# pcb-pick-plaz-ring.net
KiCad netlist of a schematic drawn in EAGLE
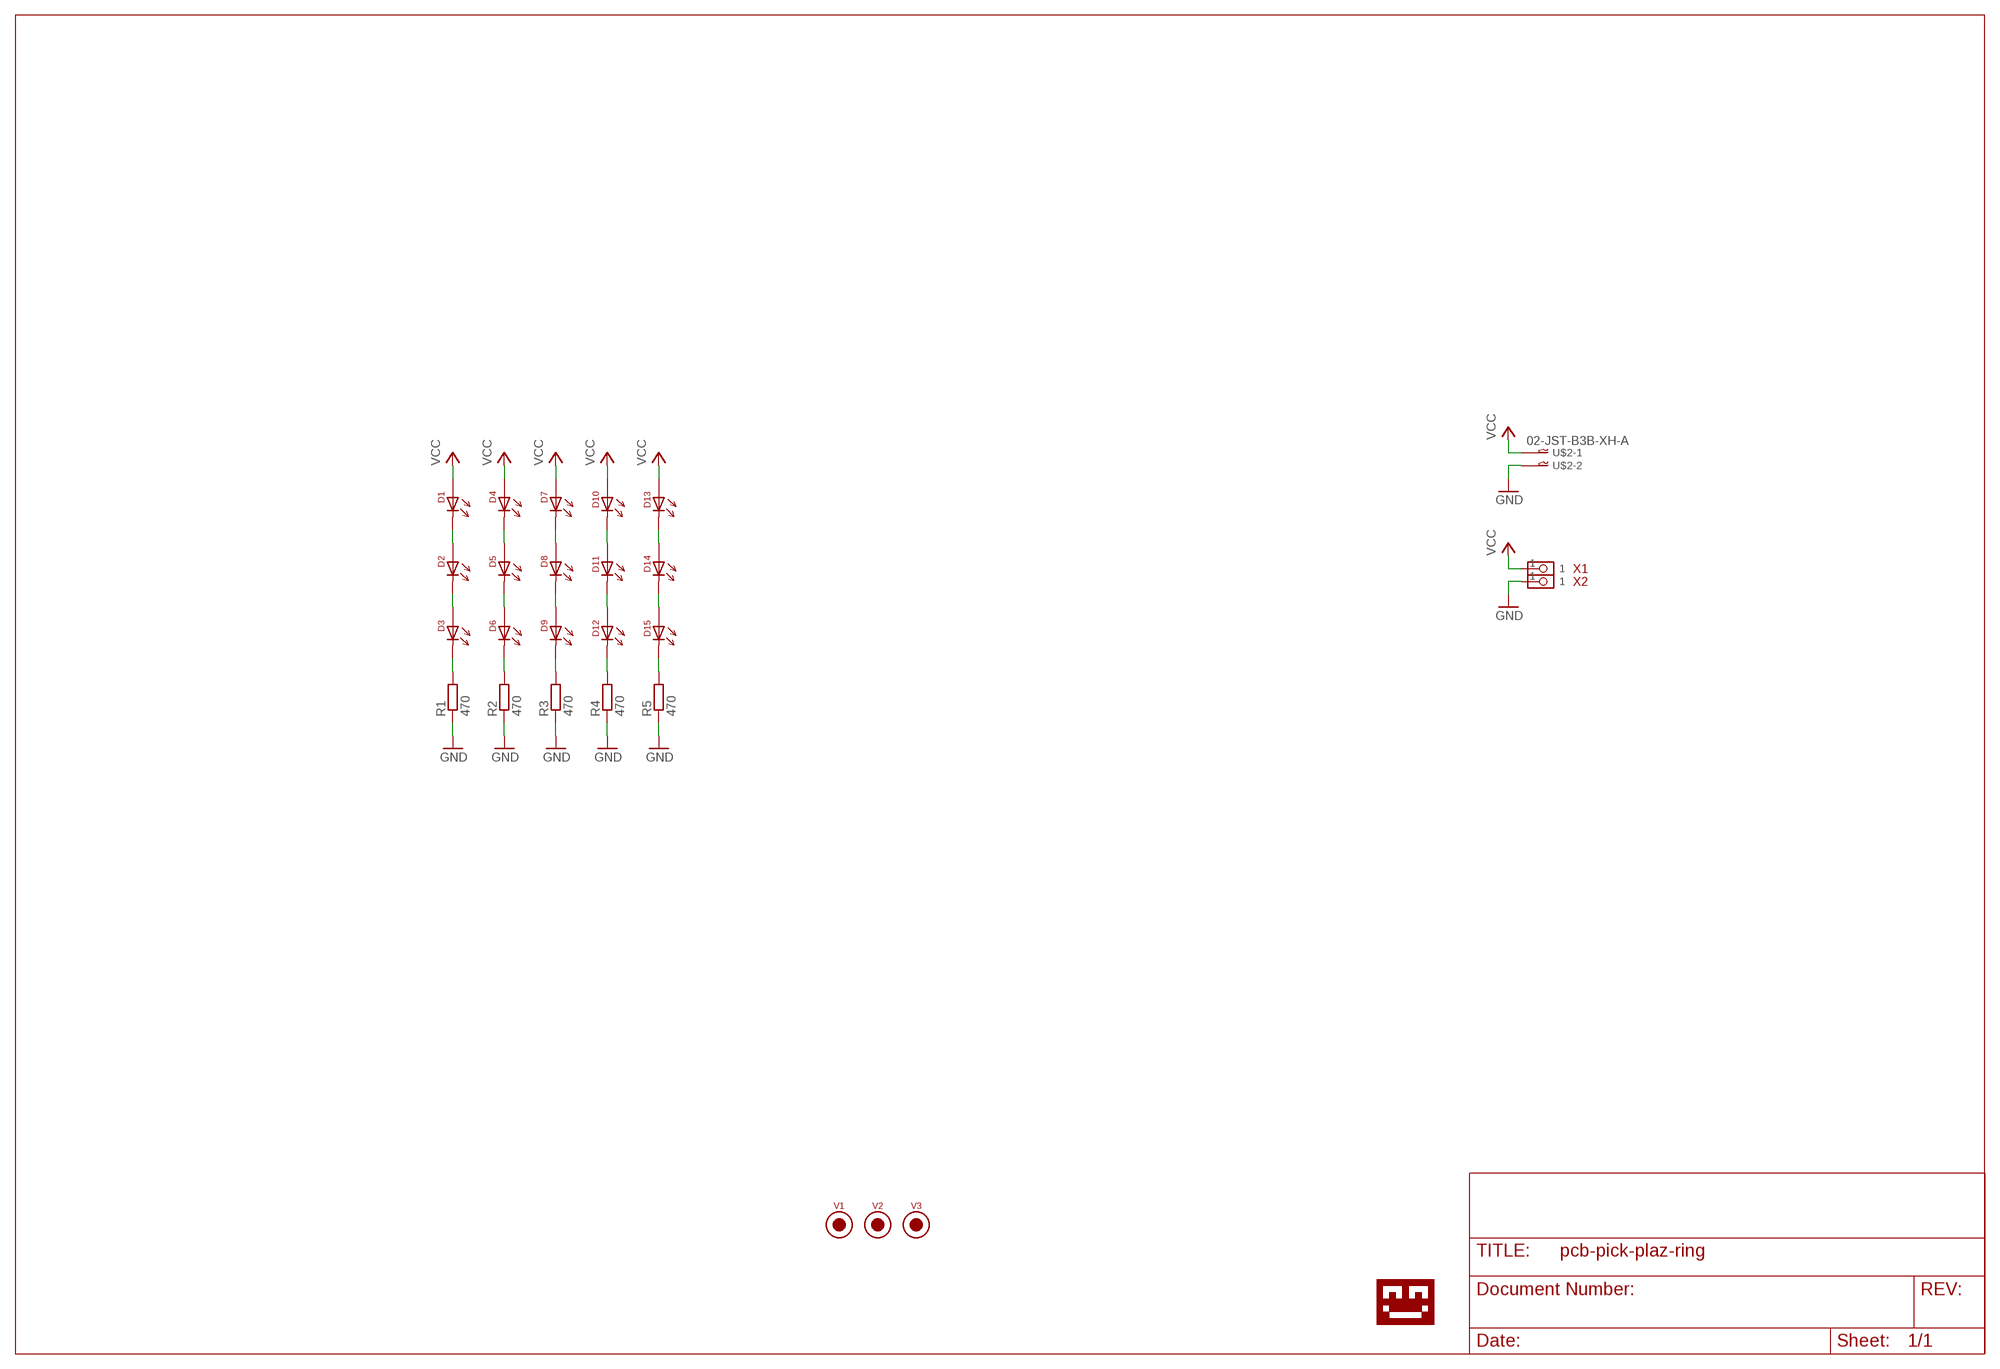
[diagram p0: schematic, sheet 1]

(export (version "E")
  (design (tool "Eeschema 10.0.6"))
  (components
    (comp (ref "D1")
      (value "LED-5730")
      (footprint "eagle-import:5730-LED")
      (libsource (lib "eagle-import") (part "LED-5730"))
    )
    (comp (ref "D2")
      (value "LED-5730")
      (footprint "eagle-import:5730-LED")
      (libsource (lib "eagle-import") (part "LED-5730"))
    )
    (comp (ref "D3")
      (value "LED-5730")
      (footprint "eagle-import:5730-LED")
      (libsource (lib "eagle-import") (part "LED-5730"))
    )
    (comp (ref "D4")
      (value "LED-5730")
      (footprint "eagle-import:5730-LED")
      (libsource (lib "eagle-import") (part "LED-5730"))
    )
    (comp (ref "D5")
      (value "LED-5730")
      (footprint "eagle-import:5730-LED")
      (libsource (lib "eagle-import") (part "LED-5730"))
    )
    (comp (ref "D6")
      (value "LED-5730")
      (footprint "eagle-import:5730-LED")
      (libsource (lib "eagle-import") (part "LED-5730"))
    )
    (comp (ref "D7")
      (value "LED-5730")
      (footprint "eagle-import:5730-LED")
      (libsource (lib "eagle-import") (part "LED-5730"))
    )
    (comp (ref "D8")
      (value "LED-5730")
      (footprint "eagle-import:5730-LED")
      (libsource (lib "eagle-import") (part "LED-5730"))
    )
    (comp (ref "D9")
      (value "LED-5730")
      (footprint "eagle-import:5730-LED")
      (libsource (lib "eagle-import") (part "LED-5730"))
    )
    (comp (ref "D10")
      (value "LED-5730")
      (footprint "eagle-import:5730-LED")
      (libsource (lib "eagle-import") (part "LED-5730"))
    )
    (comp (ref "D11")
      (value "LED-5730")
      (footprint "eagle-import:5730-LED")
      (libsource (lib "eagle-import") (part "LED-5730"))
    )
    (comp (ref "D12")
      (value "LED-5730")
      (footprint "eagle-import:5730-LED")
      (libsource (lib "eagle-import") (part "LED-5730"))
    )
    (comp (ref "D13")
      (value "LED-5730")
      (footprint "eagle-import:5730-LED")
      (libsource (lib "eagle-import") (part "LED-5730"))
    )
    (comp (ref "D14")
      (value "LED-5730")
      (footprint "eagle-import:5730-LED")
      (libsource (lib "eagle-import") (part "LED-5730"))
    )
    (comp (ref "D15")
      (value "LED-5730")
      (footprint "eagle-import:5730-LED")
      (libsource (lib "eagle-import") (part "LED-5730"))
    )
    (comp (ref "R1")
      (value "470")
      (footprint "eagle-import:0805_RES")
      (libsource (lib "eagle-import") (part "RESISTOR0805_RES"))
    )
    (comp (ref "R2")
      (value "470")
      (footprint "eagle-import:0805_RES")
      (libsource (lib "eagle-import") (part "RESISTOR0805_RES"))
    )
    (comp (ref "R3")
      (value "470")
      (footprint "eagle-import:0805_RES")
      (libsource (lib "eagle-import") (part "RESISTOR0805_RES"))
    )
    (comp (ref "R4")
      (value "470")
      (footprint "eagle-import:0805_RES")
      (libsource (lib "eagle-import") (part "RESISTOR0805_RES"))
    )
    (comp (ref "R5")
      (value "470")
      (footprint "eagle-import:0805_RES")
      (libsource (lib "eagle-import") (part "RESISTOR0805_RES"))
    )
    (comp (ref "U$1")
      (value "LOGO-TOBENG-1MM-FINISH")
      (footprint "eagle-import:TOBENG-1MM-FINISH")
      (libsource (lib "eagle-import") (part "LOGO-TOBENG-1MM-FINISH"))
    )
    (comp (ref "U$2")
      (value "02-JST-B3B-XH-A")
      (footprint "eagle-import:B2B-XH")
      (libsource (lib "eagle-import") (part "02-JST-B3B-XH-A"))
    )
    (comp (ref "V1")
      (value "FIDUCIAL2MM")
      (footprint "eagle-import:FIDUCIAL_2MM")
      (libsource (lib "eagle-import") (part "FIDUCIAL2MM"))
    )
    (comp (ref "V2")
      (value "FIDUCIAL2MM")
      (footprint "eagle-import:FIDUCIAL_2MM")
      (libsource (lib "eagle-import") (part "FIDUCIAL2MM"))
    )
    (comp (ref "V3")
      (value "FIDUCIAL2MM")
      (footprint "eagle-import:FIDUCIAL_2MM")
      (libsource (lib "eagle-import") (part "FIDUCIAL2MM"))
    )
    (comp (ref "X1")
      (value "PIN_1X1SMD_BIG_L")
      (footprint "eagle-import:PIN_1X1_SMD_BIG_L")
      (libsource (lib "eagle-import") (part "PIN_1X1SMD_BIG_L"))
    )
    (comp (ref "X2")
      (value "PIN_1X1SMD_BIG_L")
      (footprint "eagle-import:PIN_1X1_SMD_BIG_L")
      (libsource (lib "eagle-import") (part "PIN_1X1SMD_BIG_L"))
    )
  )
  (nets
    (net (code "1") (name "GND") (class "Default")
      (node (ref "R1") (pin "1") (pinfunction "1_1") (pintype "passive"))
      (node (ref "R2") (pin "1") (pinfunction "1_1") (pintype "passive"))
      (node (ref "R3") (pin "1") (pinfunction "1_1") (pintype "passive"))
      (node (ref "R4") (pin "1") (pinfunction "1_1") (pintype "passive"))
      (node (ref "R5") (pin "1") (pinfunction "1_1") (pintype "passive"))
      (node (ref "U$2") (pin "P$2") (pinfunction "1_P$2") (pintype "passive"))
      (node (ref "X2") (pin "1") (pinfunction "1_1") (pintype "bidirectional"))
    )
    (net (code "2") (name "Net-(D1-2)") (class "Default")
      (node (ref "D1") (pin "C") (pinfunction "2_C") (pintype "bidirectional"))
      (node (ref "D2") (pin "A1") (pinfunction "1_A1") (pintype "bidirectional"))
      (node (ref "D2") (pin "A2") (pinfunction "1_A2") (pintype "bidirectional"))
    )
    (net (code "3") (name "Net-(D2-2)") (class "Default")
      (node (ref "D2") (pin "C") (pinfunction "2_C") (pintype "bidirectional"))
      (node (ref "D3") (pin "A1") (pinfunction "1_A1") (pintype "bidirectional"))
      (node (ref "D3") (pin "A2") (pinfunction "1_A2") (pintype "bidirectional"))
    )
    (net (code "4") (name "Net-(D3-2)") (class "Default")
      (node (ref "D3") (pin "C") (pinfunction "2_C") (pintype "bidirectional"))
      (node (ref "R1") (pin "2") (pinfunction "2_2") (pintype "passive"))
    )
    (net (code "5") (name "Net-(D4-2)") (class "Default")
      (node (ref "D4") (pin "C") (pinfunction "2_C") (pintype "bidirectional"))
      (node (ref "D5") (pin "A1") (pinfunction "1_A1") (pintype "bidirectional"))
      (node (ref "D5") (pin "A2") (pinfunction "1_A2") (pintype "bidirectional"))
    )
    (net (code "6") (name "Net-(D5-2)") (class "Default")
      (node (ref "D5") (pin "C") (pinfunction "2_C") (pintype "bidirectional"))
      (node (ref "D6") (pin "A1") (pinfunction "1_A1") (pintype "bidirectional"))
      (node (ref "D6") (pin "A2") (pinfunction "1_A2") (pintype "bidirectional"))
    )
    (net (code "7") (name "Net-(D6-2)") (class "Default")
      (node (ref "D6") (pin "C") (pinfunction "2_C") (pintype "bidirectional"))
      (node (ref "R2") (pin "2") (pinfunction "2_2") (pintype "passive"))
    )
    (net (code "8") (name "Net-(D7-2)") (class "Default")
      (node (ref "D7") (pin "C") (pinfunction "2_C") (pintype "bidirectional"))
      (node (ref "D8") (pin "A1") (pinfunction "1_A1") (pintype "bidirectional"))
      (node (ref "D8") (pin "A2") (pinfunction "1_A2") (pintype "bidirectional"))
    )
    (net (code "9") (name "Net-(D8-2)") (class "Default")
      (node (ref "D8") (pin "C") (pinfunction "2_C") (pintype "bidirectional"))
      (node (ref "D9") (pin "A1") (pinfunction "1_A1") (pintype "bidirectional"))
      (node (ref "D9") (pin "A2") (pinfunction "1_A2") (pintype "bidirectional"))
    )
    (net (code "10") (name "Net-(D9-2)") (class "Default")
      (node (ref "D9") (pin "C") (pinfunction "2_C") (pintype "bidirectional"))
      (node (ref "R3") (pin "2") (pinfunction "2_2") (pintype "passive"))
    )
    (net (code "11") (name "Net-(D10-2)") (class "Default")
      (node (ref "D10") (pin "C") (pinfunction "2_C") (pintype "bidirectional"))
      (node (ref "D11") (pin "A1") (pinfunction "1_A1") (pintype "bidirectional"))
      (node (ref "D11") (pin "A2") (pinfunction "1_A2") (pintype "bidirectional"))
    )
    (net (code "12") (name "Net-(D11-2)") (class "Default")
      (node (ref "D11") (pin "C") (pinfunction "2_C") (pintype "bidirectional"))
      (node (ref "D12") (pin "A1") (pinfunction "1_A1") (pintype "bidirectional"))
      (node (ref "D12") (pin "A2") (pinfunction "1_A2") (pintype "bidirectional"))
    )
    (net (code "13") (name "Net-(D12-2)") (class "Default")
      (node (ref "D12") (pin "C") (pinfunction "2_C") (pintype "bidirectional"))
      (node (ref "R4") (pin "2") (pinfunction "2_2") (pintype "passive"))
    )
    (net (code "14") (name "Net-(D13-2)") (class "Default")
      (node (ref "D13") (pin "C") (pinfunction "2_C") (pintype "bidirectional"))
      (node (ref "D14") (pin "A1") (pinfunction "1_A1") (pintype "bidirectional"))
      (node (ref "D14") (pin "A2") (pinfunction "1_A2") (pintype "bidirectional"))
    )
    (net (code "15") (name "Net-(D14-2)") (class "Default")
      (node (ref "D14") (pin "C") (pinfunction "2_C") (pintype "bidirectional"))
      (node (ref "D15") (pin "A1") (pinfunction "1_A1") (pintype "bidirectional"))
      (node (ref "D15") (pin "A2") (pinfunction "1_A2") (pintype "bidirectional"))
    )
    (net (code "16") (name "Net-(D15-2)") (class "Default")
      (node (ref "D15") (pin "C") (pinfunction "2_C") (pintype "bidirectional"))
      (node (ref "R5") (pin "2") (pinfunction "2_2") (pintype "passive"))
    )
    (net (code "17") (name "VCC") (class "Default")
      (node (ref "D1") (pin "A1") (pinfunction "1_A1") (pintype "bidirectional"))
      (node (ref "D1") (pin "A2") (pinfunction "1_A2") (pintype "bidirectional"))
      (node (ref "D10") (pin "A1") (pinfunction "1_A1") (pintype "bidirectional"))
      (node (ref "D10") (pin "A2") (pinfunction "1_A2") (pintype "bidirectional"))
      (node (ref "D13") (pin "A1") (pinfunction "1_A1") (pintype "bidirectional"))
      (node (ref "D13") (pin "A2") (pinfunction "1_A2") (pintype "bidirectional"))
      (node (ref "D4") (pin "A1") (pinfunction "1_A1") (pintype "bidirectional"))
      (node (ref "D4") (pin "A2") (pinfunction "1_A2") (pintype "bidirectional"))
      (node (ref "D7") (pin "A1") (pinfunction "1_A1") (pintype "bidirectional"))
      (node (ref "D7") (pin "A2") (pinfunction "1_A2") (pintype "bidirectional"))
      (node (ref "U$2") (pin "P$1") (pinfunction "1_P$1") (pintype "passive"))
      (node (ref "X1") (pin "1") (pinfunction "1_1") (pintype "bidirectional"))
    )
  )
)
